# Sheet1.net
KiCad netlist of a schematic drawn in Altium Designer
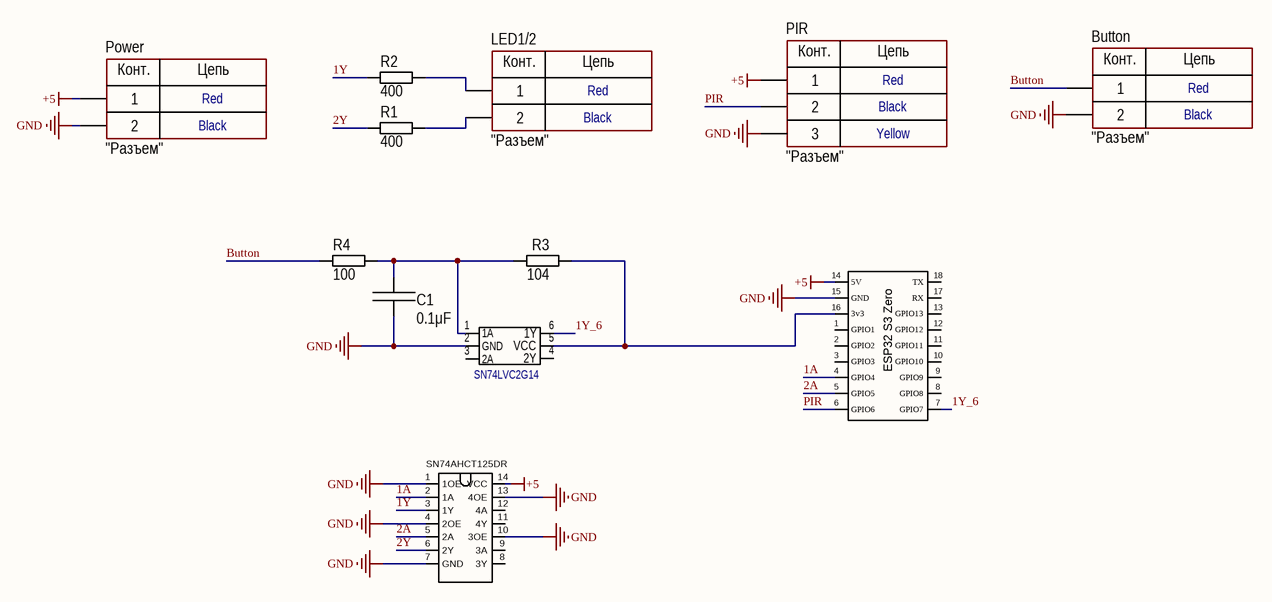
[diagram p0: Sheet1.SchDoc]

(export (version "E")
  (design (tool "Eeschema 10.0.6"))
  (components
    (comp (ref "*")
      (value "SN74AHCT125DR")
      (footprint "14-SOIC")
      (libsource (lib "IC. Logic") (part "SN74AHCT125DR"))
    )
    (comp (ref "Button")
      (value "~")
      (footprint "CON: CWF-2")
      (fields
        (field (name "MANUFACTURER") "Connfly")
        (field (name "VALUEMANUFACTURERPARTNUMBER") "Connector, 2pin, 2.54mm, 250VAC, 3A")
        (field (name "PARTNUMBER") "CWF-2R")
        (field (name "COMMENTTEXT") "\"Разъем\"")
      )
      (libsource (lib "") (part "CWF-2_1"))
    )
    (comp (ref "C1")
      (value "0.1μF")
      (footprint "CAP: 0805")
      (fields
        (field (name "MANUFACTURER") "Yageo")
        (field (name "PARTNUMBER") "CC0805KRX7R7BB104")
        (field (name "VALUEMANUFACTURERPARTNUMBER") "Ceramic capacitor, 0.1μF, X7R, ±10%, 16V, 0805, -55...+125°C")
      )
      (libsource (lib "Capacitor") (part "Ceramic_0805"))
    )
    (comp (ref "LED1/2")
      (value "~")
      (footprint "CON: CWF-2")
      (fields
        (field (name "MANUFACTURER") "Connfly")
        (field (name "VALUEMANUFACTURERPARTNUMBER") "Connector, 2pin, 2.54mm, 250VAC, 3A")
        (field (name "PARTNUMBER") "CWF-2R")
        (field (name "COMMENTTEXT") "\"Разъем\"")
      )
      (libsource (lib "") (part "CWF-2_2"))
    )
    (comp (ref "PIR")
      (value "~")
      (footprint "CON: CWF-3")
      (fields
        (field (name "MANUFACTURER") "Connfly")
        (field (name "VALUEMANUFACTURERPARTNUMBER") "Connector, 2pin, 2.54mm, 250VAC, 3A")
        (field (name "PARTNUMBER") "CWF-2R")
        (field (name "COMMENTTEXT") "\"Разъем\"")
      )
      (libsource (lib "Connector") (part "CWF-3"))
    )
    (comp (ref "Power")
      (value "~")
      (footprint "CON: CWF-2")
      (fields
        (field (name "MANUFACTURER") "Connfly")
        (field (name "VALUEMANUFACTURERPARTNUMBER") "Connector, 2pin, 2.54mm, 250VAC, 3A")
        (field (name "PARTNUMBER") "CWF-2R")
        (field (name "COMMENTTEXT") "\"Разъем\"")
      )
      (libsource (lib "Connector") (part "CWF-2"))
    )
    (comp (ref "pp")
      (value "ESP32 S3 Zero")
      (footprint "ESP32 S3 Zero")
      (libsource (lib "MyLib") (part "ESP32 S3 Zero"))
    )
    (comp (ref "R1")
      (value "400")
      (footprint "RES: 0805")
      (fields
        (field (name "MANUFACTURER") "Yageo")
        (field (name "PARTNUMBER") "RC0805JR-07100RL")
        (field (name "VALUEMANUFACTURERPARTNUMBER") "Resistor film, 400, ±5%, 0805, 0.125W, -55...+125°C")
      )
      (libsource (lib "Resistor") (part "Resistor_0805"))
    )
    (comp (ref "R2")
      (value "400")
      (footprint "RES: 0805")
      (fields
        (field (name "MANUFACTURER") "Yageo")
        (field (name "PARTNUMBER") "RC0805JR-07100RL")
        (field (name "VALUEMANUFACTURERPARTNUMBER") "Resistor film, 400, ±5%, 0805, 0.125W, -55...+125°C")
      )
      (libsource (lib "Resistor") (part "Resistor_0805"))
    )
    (comp (ref "R3")
      (value "104")
      (footprint "RES: 0805")
      (fields
        (field (name "MANUFACTURER") "Yageo")
        (field (name "PARTNUMBER") "RC0805JR-07100RL")
        (field (name "VALUEMANUFACTURERPARTNUMBER") "Resistor film, 104, ±5%, 0805, 0.125W, -55...+125°C")
      )
      (libsource (lib "") (part "Resistor_0805_1"))
    )
    (comp (ref "R4")
      (value "100")
      (footprint "RES: 0805")
      (fields
        (field (name "MANUFACTURER") "Yageo")
        (field (name "PARTNUMBER") "RC0805JR-07100RL")
        (field (name "VALUEMANUFACTURERPARTNUMBER") "Resistor film, 100, ±5%, 0805, 0.125W, -55...+125°C")
      )
      (libsource (lib "Resistor") (part "Resistor_0805"))
    )
    (comp (ref "SN74LVC2G14")
      (value "Dual Schmitt-Trigger Inverter")
      (footprint "SOT23-6")
      (description "Invertor")
      (libsource (lib "IC. Logic") (part "SN74LVC2G14DBVR"))
    )
  )
  (nets
    (net (code "1") (name "+5") (class "Default")
      (node (ref "*") (pin "14") (pinfunction "VCC_14") (pintype "passive"))
      (node (ref "PIR") (pin "1") (pinfunction "1_1") (pintype "passive"))
      (node (ref "Power") (pin "1") (pinfunction "1_1") (pintype "passive"))
      (node (ref "pp") (pin "14") (pinfunction "5V_14") (pintype "passive"))
    )
    (net (code "2") (name "/1A") (class "Default")
      (node (ref "*") (pin "2") (pinfunction "1A_2") (pintype "passive"))
      (node (ref "pp") (pin "4") (pinfunction "GPIO4_4") (pintype "passive"))
    )
    (net (code "3") (name "/1Y") (class "Default")
      (node (ref "*") (pin "3") (pinfunction "1Y_3") (pintype "passive"))
      (node (ref "R2") (pin "1") (pinfunction "1_1") (pintype "passive"))
    )
    (net (code "4") (name "/1Y_6") (class "Default")
      (node (ref "SN74LVC2G14") (pin "6") (pinfunction "1Y_6") (pintype "passive"))
      (node (ref "pp") (pin "7") (pinfunction "GPIO7_7") (pintype "passive"))
    )
    (net (code "5") (name "/2A") (class "Default")
      (node (ref "*") (pin "5") (pinfunction "2A_5") (pintype "passive"))
      (node (ref "pp") (pin "5") (pinfunction "GPIO5_5") (pintype "passive"))
    )
    (net (code "6") (name "/2Y") (class "Default")
      (node (ref "*") (pin "6") (pinfunction "2Y_6") (pintype "passive"))
      (node (ref "R1") (pin "1") (pinfunction "1_1") (pintype "passive"))
    )
    (net (code "7") (name "/Button") (class "Default")
      (node (ref "Button") (pin "1") (pinfunction "1_1") (pintype "passive"))
      (node (ref "R4") (pin "1") (pinfunction "1_1") (pintype "passive"))
    )
    (net (code "8") (name "/PIR") (class "Default")
      (node (ref "PIR") (pin "2") (pinfunction "2_2") (pintype "passive"))
      (node (ref "pp") (pin "6") (pinfunction "GPIO6_6") (pintype "passive"))
    )
    (net (code "9") (name "GND") (class "Default")
      (node (ref "*") (pin "1") (pinfunction "1OE_1") (pintype "passive"))
      (node (ref "*") (pin "10") (pinfunction "3OE_10") (pintype "passive"))
      (node (ref "*") (pin "13") (pinfunction "4OE_13") (pintype "passive"))
      (node (ref "*") (pin "4") (pinfunction "2OE_4") (pintype "passive"))
      (node (ref "*") (pin "7") (pinfunction "GND_7") (pintype "passive"))
      (node (ref "Button") (pin "2") (pinfunction "2_2") (pintype "passive"))
      (node (ref "C1") (pin "1") (pinfunction "1_1") (pintype "power_in"))
      (node (ref "PIR") (pin "3") (pinfunction "3_3") (pintype "passive"))
      (node (ref "Power") (pin "2") (pinfunction "2_2") (pintype "passive"))
      (node (ref "SN74LVC2G14") (pin "2") (pinfunction "GND_2") (pintype "passive"))
      (node (ref "pp") (pin "15") (pinfunction "GND_15") (pintype "passive"))
    )
    (net (code "10") (name "Net-(LED1/2-Pad1)") (class "Default")
      (node (ref "LED1/2") (pin "1") (pinfunction "1_1") (pintype "passive"))
      (node (ref "R2") (pin "2") (pinfunction "2_2") (pintype "passive"))
    )
    (net (code "11") (name "Net-(LED1/2-Pad2)") (class "Default")
      (node (ref "LED1/2") (pin "2") (pinfunction "2_2") (pintype "passive"))
      (node (ref "R1") (pin "2") (pinfunction "2_2") (pintype "passive"))
    )
    (net (code "12") (name "Net-(SN74LVC2G14-1A)") (class "Default")
      (node (ref "C1") (pin "2") (pinfunction "2_2") (pintype "power_in"))
      (node (ref "R3") (pin "2") (pinfunction "2_2") (pintype "passive"))
      (node (ref "R4") (pin "2") (pinfunction "2_2") (pintype "passive"))
      (node (ref "SN74LVC2G14") (pin "1") (pinfunction "1A_1") (pintype "passive"))
    )
    (net (code "13") (name "Net-(SN74LVC2G14-VCC)") (class "Default")
      (node (ref "R3") (pin "1") (pinfunction "1_1") (pintype "passive"))
      (node (ref "SN74LVC2G14") (pin "5") (pinfunction "VCC_5") (pintype "passive"))
      (node (ref "pp") (pin "16") (pinfunction "3v3_16") (pintype "passive"))
    )
    (net (code "14") (name "unconnected-(*-3A-Pad9)") (class "Default")
      (node (ref "*") (pin "9") (pinfunction "3A_9") (pintype "passive"))
    )
    (net (code "15") (name "unconnected-(*-3Y-Pad8)") (class "Default")
      (node (ref "*") (pin "8") (pinfunction "3Y_8") (pintype "passive"))
    )
    (net (code "16") (name "unconnected-(*-4A-Pad12)") (class "Default")
      (node (ref "*") (pin "12") (pinfunction "4A_12") (pintype "passive"))
    )
    (net (code "17") (name "unconnected-(*-4Y-Pad11)") (class "Default")
      (node (ref "*") (pin "11") (pinfunction "4Y_11") (pintype "passive"))
    )
    (net (code "18") (name "unconnected-(SN74LVC2G14-2A-Pad3)") (class "Default")
      (node (ref "SN74LVC2G14") (pin "3") (pinfunction "2A_3") (pintype "passive"))
    )
    (net (code "19") (name "unconnected-(SN74LVC2G14-2Y-Pad4)") (class "Default")
      (node (ref "SN74LVC2G14") (pin "4") (pinfunction "2Y_4") (pintype "passive"))
    )
    (net (code "20") (name "unconnected-(pp-GPIO1-Pad1)") (class "Default")
      (node (ref "pp") (pin "1") (pinfunction "GPIO1_1") (pintype "passive"))
    )
    (net (code "21") (name "unconnected-(pp-GPIO2-Pad2)") (class "Default")
      (node (ref "pp") (pin "2") (pinfunction "GPIO2_2") (pintype "passive"))
    )
    (net (code "22") (name "unconnected-(pp-GPIO3-Pad3)") (class "Default")
      (node (ref "pp") (pin "3") (pinfunction "GPIO3_3") (pintype "passive"))
    )
    (net (code "23") (name "unconnected-(pp-GPIO8-Pad8)") (class "Default")
      (node (ref "pp") (pin "8") (pinfunction "GPIO8_8") (pintype "passive"))
    )
    (net (code "24") (name "unconnected-(pp-GPIO9-Pad9)") (class "Default")
      (node (ref "pp") (pin "9") (pinfunction "GPIO9_9") (pintype "passive"))
    )
    (net (code "25") (name "unconnected-(pp-GPIO10-Pad10)") (class "Default")
      (node (ref "pp") (pin "10") (pinfunction "GPIO10_10") (pintype "passive"))
    )
    (net (code "26") (name "unconnected-(pp-GPIO11-Pad11)") (class "Default")
      (node (ref "pp") (pin "11") (pinfunction "GPIO11_11") (pintype "passive"))
    )
    (net (code "27") (name "unconnected-(pp-GPIO12-Pad12)") (class "Default")
      (node (ref "pp") (pin "12") (pinfunction "GPIO12_12") (pintype "passive"))
    )
    (net (code "28") (name "unconnected-(pp-GPIO13-Pad13)") (class "Default")
      (node (ref "pp") (pin "13") (pinfunction "GPIO13_13") (pintype "passive"))
    )
    (net (code "29") (name "unconnected-(pp-RX-Pad17)") (class "Default")
      (node (ref "pp") (pin "17") (pinfunction "RX_17") (pintype "passive"))
    )
    (net (code "30") (name "unconnected-(pp-TX-Pad18)") (class "Default")
      (node (ref "pp") (pin "18") (pinfunction "TX_18") (pintype "passive"))
    )
  )
)
